# 01-Power.net
KiCad netlist of a schematic drawn in Altium Designer
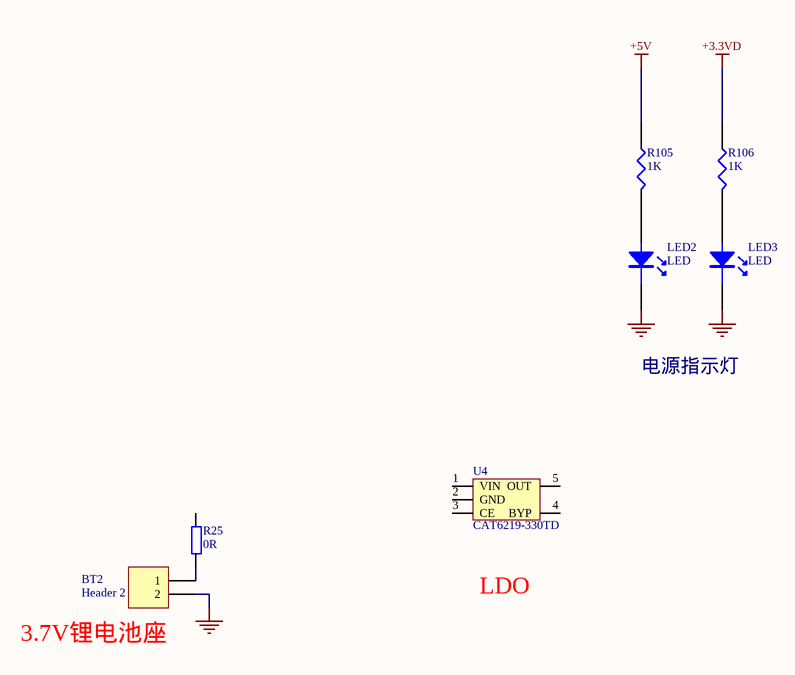
[diagram p0: 01-Power.SchDoc]

(export (version "E")
  (design (tool "Eeschema 10.0.6"))
  (components
    (comp (ref "BT2")
      (value "Header 2")
      (footprint "HDR1X2")
      (description "Header, 2-Pin")
      (fields (field (name "PUBLISHER") "Altium Limited"))
      (libsource (lib "Miscellaneous Connectors") (part "Header 2"))
    )
    (comp (ref "LED2") (value "LED") (footprint "LED0805") (libsource (lib "*") (part "LED")))
    (comp (ref "LED3") (value "LED") (footprint "LED0805") (libsource (lib "*") (part "LED")))
    (comp (ref "R25") (value "0R") (footprint "0603") (libsource (lib "STM32F429_Core_V1.0") (part "R")))
    (comp (ref "R105") (value "1K") (footprint "0805") (libsource (lib "*") (part "RES1")))
    (comp (ref "R106") (value "1K") (footprint "0805") (libsource (lib "*") (part "RES1")))
    (comp (ref "U4")
      (value "CAT6219-330TD")
      (footprint "SOT-23-5")
      (description "3.3V 500mA LDO")
      (libsource (lib "Miscellaneous Devices") (part "CAT6219-330TD"))
    )
  )
  (nets
    (net (code "1") (name "+3.3VD") (class "Default")
      (node (ref "R106") (pin "1") (pinfunction "1_1") (pintype "passive"))
    )
    (net (code "2") (name "+5V") (class "Default")
      (node (ref "R105") (pin "1") (pinfunction "1_1") (pintype "passive"))
    )
    (net (code "3") (name "DGND") (class "Default")
      (node (ref "BT2") (pin "2") (pinfunction "2_2") (pintype "passive"))
      (node (ref "LED2") (pin "2") (pinfunction "K_2") (pintype "passive"))
      (node (ref "LED3") (pin "2") (pinfunction "K_2") (pintype "passive"))
    )
    (net (code "4") (name "Net-(BT2-Pad1)") (class "Default")
      (node (ref "BT2") (pin "1") (pinfunction "1_1") (pintype "passive"))
      (node (ref "R25") (pin "1") (pintype "passive"))
    )
    (net (code "5") (name "Net-(LED2-A)") (class "Default")
      (node (ref "LED2") (pin "1") (pinfunction "A_1") (pintype "passive"))
      (node (ref "R105") (pin "2") (pinfunction "2_2") (pintype "passive"))
    )
    (net (code "6") (name "Net-(LED3-A)") (class "Default")
      (node (ref "LED3") (pin "1") (pinfunction "A_1") (pintype "passive"))
      (node (ref "R106") (pin "2") (pinfunction "2_2") (pintype "passive"))
    )
    (net (code "7") (name "unconnected-(R25-Pad2)") (class "Default")
      (node (ref "R25") (pin "2") (pintype "passive"))
    )
    (net (code "8") (name "unconnected-(U4-BYP-Pad4)") (class "Default")
      (node (ref "U4") (pin "4") (pinfunction "BYP_4") (pintype "passive"))
    )
    (net (code "9") (name "unconnected-(U4-CE-Pad3)") (class "Default")
      (node (ref "U4") (pin "3") (pinfunction "CE_3") (pintype "passive"))
    )
    (net (code "10") (name "unconnected-(U4-GND-Pad2)") (class "Default")
      (node (ref "U4") (pin "2") (pinfunction "GND_2") (pintype "passive"))
    )
    (net (code "11") (name "unconnected-(U4-OUT-Pad5)") (class "Default")
      (node (ref "U4") (pin "5") (pinfunction "OUT_5") (pintype "passive"))
    )
    (net (code "12") (name "unconnected-(U4-VIN-Pad1)") (class "Default")
      (node (ref "U4") (pin "1") (pinfunction "VIN_1") (pintype "passive"))
    )
  )
)
